# Version_2018_01.net
KiCad netlist of a schematic drawn in Altium Designer
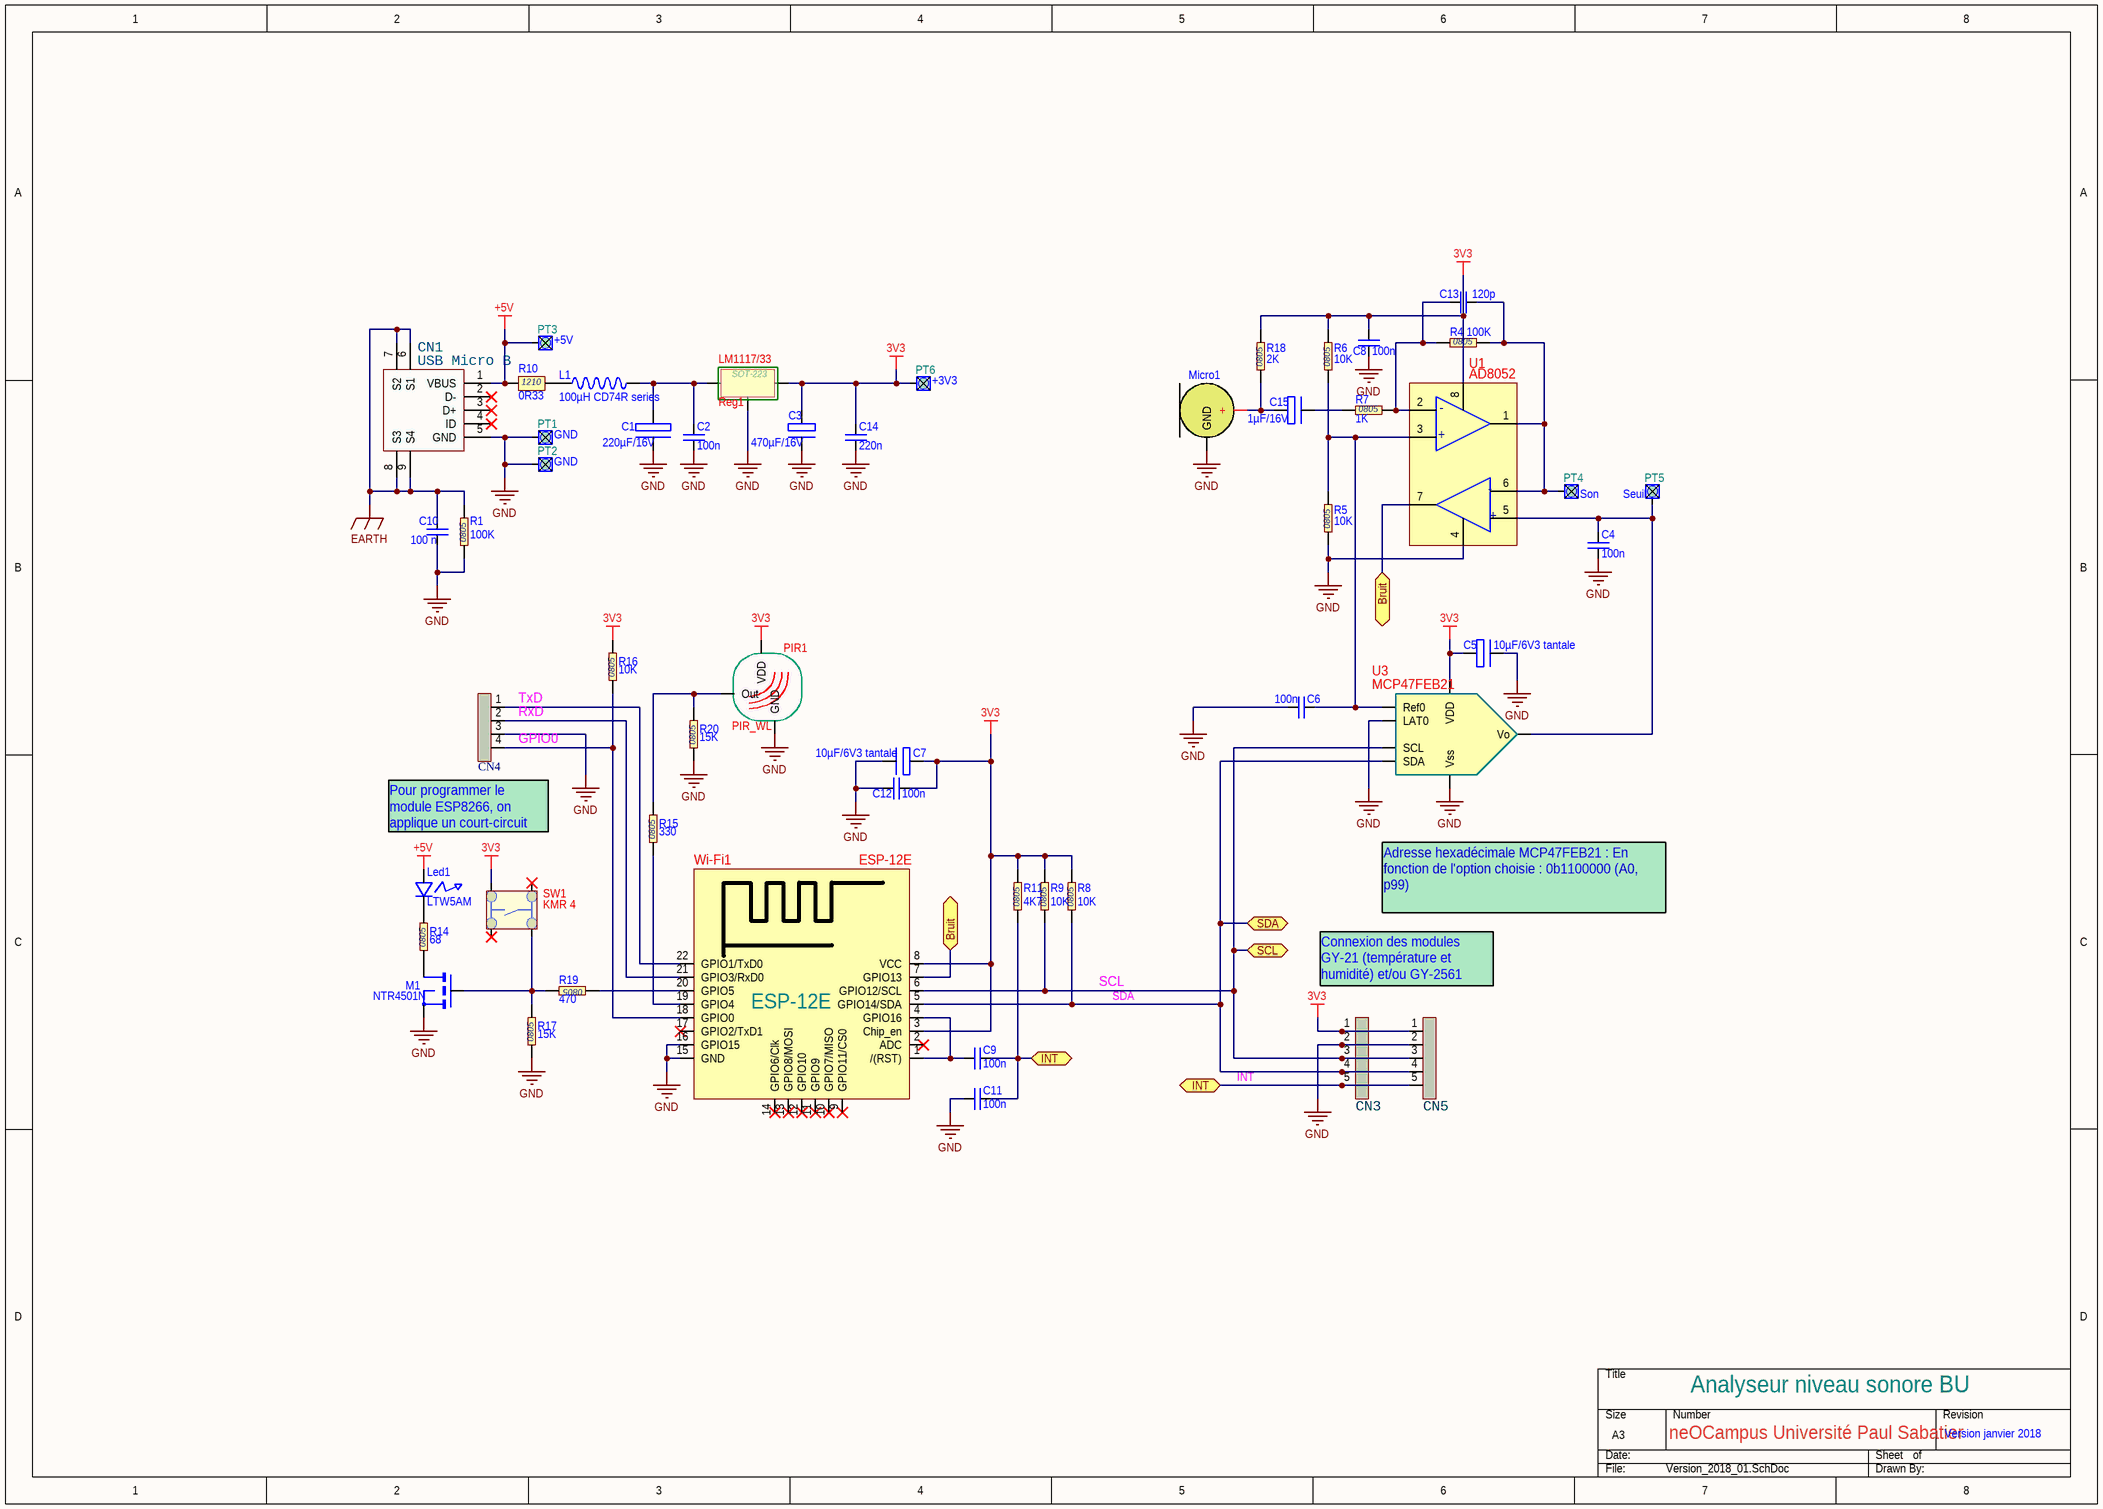
[diagram p0: Version_2018_01.SchDoc]

(export (version "E")
  (design (tool "Eeschema 10.0.6"))
  (components
    (comp (ref "C1")
      (value "220µF/16V")
      (footprint "7343-31")
      (description "253-5290 case 7343-31")
      (libsource (lib "CMS") (part "tantale 220µF/16V"))
    )
    (comp (ref "C2")
      (value "100n")
      (footprint "0805")
      (description "CMS 0805")
      (libsource (lib "CMS") (part "Cap_CMS_0805"))
    )
    (comp (ref "C3")
      (value "470µF/16V")
      (footprint "47µF/16V")
      (description "électrochimique diam. 6,3mm 128-1810")
      (libsource (lib "traversants") (part "47µF/16V"))
    )
    (comp (ref "C4")
      (value "100n")
      (footprint "0805")
      (description "CMS 0805")
      (libsource (lib "CMS") (part "Cap_CMS_0805"))
    )
    (comp (ref "C5")
      (value "10µF/6V3 tantale")
      (footprint "Tantale 10µF/6V3")
      (description "175-4041 ou 145-7412 case 3216-18")
      (libsource (lib "CMS") (part "tantale 10µF/6V3"))
    )
    (comp (ref "C6")
      (value "100n")
      (footprint "0805")
      (description "CMS 0805")
      (libsource (lib "CMS") (part "Cap_CMS_0805"))
    )
    (comp (ref "C7")
      (value "10µF/6V3 tantale")
      (footprint "Tantale 10µF/6V3")
      (description "175-4041 ou 145-7412 case 3216-18")
      (libsource (lib "CMS") (part "tantale 10µF/6V3"))
    )
    (comp (ref "C8")
      (value "100n")
      (footprint "0805")
      (description "CMS 0805")
      (libsource (lib "CMS") (part "Cap_CMS_0805"))
    )
    (comp (ref "C9")
      (value "100n")
      (footprint "0805")
      (description "CMS 0805")
      (libsource (lib "CMS") (part "Cap_CMS_0805"))
    )
    (comp (ref "C10")
      (value "100 n")
      (footprint "0805")
      (description "CMS 0805")
      (libsource (lib "CMS") (part "Cap_CMS_0805"))
    )
    (comp (ref "C11")
      (value "100n")
      (footprint "0805")
      (description "CMS 0805")
      (libsource (lib "CMS") (part "Cap_CMS_0805"))
    )
    (comp (ref "C12")
      (value "100n")
      (footprint "0805")
      (description "CMS 0805")
      (libsource (lib "CMS") (part "Cap_CMS_0805"))
    )
    (comp (ref "C13")
      (value "120p")
      (footprint "0805")
      (description "CMS 0805")
      (libsource (lib "CMS") (part "Cap_CMS_0805"))
    )
    (comp (ref "C14")
      (value "220n")
      (footprint "0805")
      (description "CMS 0805")
      (libsource (lib "CMS") (part "Cap_CMS_0805"))
    )
    (comp (ref "C15")
      (value "1µF/16V")
      (footprint "3216-18")
      (description "145-7406 case 3216-18")
      (libsource (lib "CMS") (part "tantale 1µF/16V"))
    )
    (comp (ref "CN1")
      (value "USB Micro B")
      (footprint "USB Micro 714-2347")
      (description "Amphenol 714-2347")
      (libsource (lib "Connecteurs Contacts") (part "USB Micro B"))
    )
    (comp (ref "CN3")
      (value "inch_ligne 1x5")
      (footprint "INCH_1x5_droit")
      (description "Inch_1x5_droit")
      (libsource (lib "Connecteurs Contacts") (part "Inch_1x5_droit"))
    )
    (comp (ref "CN4")
      (value "inch_ligne 1x4")
      (footprint "INCH_1x4_droit")
      (description "Inch_1x4_droit")
      (libsource (lib "Connecteurs Contacts") (part "Inch_1x4_droit"))
    )
    (comp (ref "CN5")
      (value "inch_ligne 1x5")
      (footprint "INCH_1x5_droit")
      (description "Inch_1x5_droit")
      (libsource (lib "Connecteurs Contacts") (part "Inch_1x5_droit"))
    )
    (comp (ref "L1")
      (value "100µH CD74R series")
      (footprint "SELF CD74R")
      (description "SMT CD74R Aliexpress")
      (libsource (lib "CMS") (part "Self CD74R"))
    )
    (comp (ref "Led1")
      (value "LTW5AM")
      (footprint "LTW5AM")
      (description "LED Golden Dragon Plus")
      (libsource (lib "CMS") (part "LTW5AM LED"))
    )
    (comp (ref "M1")
      (value "NTR4501N")
      (footprint "SOT23 (NTR4501)")
      (description "MOSFET canal N")
      (libsource (lib "Transistors Bip Mos IGBT") (part "NTR4501N"))
    )
    (comp (ref "Micro1")
      (value "Electret")
      (footprint "Micro_electret simple")
      (description "Microphone électret")
      (libsource (lib "traversants") (part "Microphone_03"))
    )
    (comp (ref "PIR1")
      (value "PIR_WL")
      (footprint "PIR_WL")
      (description "Détecteur infrarouge")
      (libsource (lib "traversants") (part "PIR_01"))
    )
    (comp (ref "PT1")
      (value "GND")
      (footprint "PTEST boucle")
      (description "pointe de test CI 262-2179")
      (libsource (lib "Connecteurs Contacts") (part "PTEST boucle"))
    )
    (comp (ref "PT2")
      (value "GND")
      (footprint "PTEST boucle")
      (description "pointe de test CI 262-2179")
      (libsource (lib "Connecteurs Contacts") (part "PTEST boucle"))
    )
    (comp (ref "PT3")
      (value "+5V")
      (footprint "PTEST boucle")
      (description "pointe de test CI 262-2179")
      (libsource (lib "Connecteurs Contacts") (part "PTEST boucle"))
    )
    (comp (ref "PT4")
      (value "Son")
      (footprint "PTEST boucle")
      (description "pointe de test CI 262-2179")
      (libsource (lib "Connecteurs Contacts") (part "PTEST boucle"))
    )
    (comp (ref "PT5")
      (value "Seuil")
      (footprint "PTEST boucle")
      (description "pointe de test CI 262-2179")
      (libsource (lib "Connecteurs Contacts") (part "PTEST boucle"))
    )
    (comp (ref "PT6")
      (value "+3V3")
      (footprint "PTEST boucle")
      (description "pointe de test CI 262-2179")
      (libsource (lib "Connecteurs Contacts") (part "PTEST boucle"))
    )
    (comp (ref "R1")
      (value "100K")
      (footprint "0805")
      (description "CMS 0805")
      (libsource (lib "") (part "Res CMS 0805_1"))
    )
    (comp (ref "R4")
      (value "100K")
      (footprint "0805")
      (description "CMS 0805")
      (libsource (lib "CMS") (part "Res CMS 0805"))
    )
    (comp (ref "R5")
      (value "10K")
      (footprint "0805")
      (description "CMS 0805")
      (libsource (lib "") (part "Res CMS 0805_1"))
    )
    (comp (ref "R6")
      (value "10K")
      (footprint "0805")
      (description "CMS 0805")
      (libsource (lib "") (part "Res CMS 0805_1"))
    )
    (comp (ref "R7")
      (value "1K")
      (footprint "0805")
      (description "CMS 0805")
      (libsource (lib "CMS") (part "Res CMS 0805"))
    )
    (comp (ref "R8")
      (value "10K")
      (footprint "0805")
      (description "CMS 0805")
      (libsource (lib "") (part "Res CMS 0805_1"))
    )
    (comp (ref "R9")
      (value "10K")
      (footprint "0805")
      (description "CMS 0805")
      (libsource (lib "") (part "Res CMS 0805_1"))
    )
    (comp (ref "R10")
      (value "0R33")
      (footprint "1210")
      (description "CMS 1210")
      (libsource (lib "CMS") (part "Res CMS 1210 ERJ14B"))
    )
    (comp (ref "R11")
      (value "4K7")
      (footprint "0805")
      (description "CMS 0805")
      (libsource (lib "") (part "Res CMS 0805_1"))
    )
    (comp (ref "R14")
      (value "68")
      (footprint "0805")
      (description "CMS 0805")
      (libsource (lib "") (part "Res CMS 0805_1"))
    )
    (comp (ref "R15")
      (value "330")
      (footprint "0805")
      (description "CMS 0805")
      (libsource (lib "") (part "Res CMS 0805_1"))
    )
    (comp (ref "R16")
      (value "10K")
      (footprint "0805")
      (description "CMS 0805")
      (libsource (lib "") (part "Res CMS 0805_1"))
    )
    (comp (ref "R17")
      (value "15K")
      (footprint "0805")
      (description "CMS 0805")
      (libsource (lib "") (part "Res CMS 0805_1"))
    )
    (comp (ref "R18")
      (value "2K")
      (footprint "0805")
      (description "CMS 0805")
      (libsource (lib "") (part "Res CMS 0805_1"))
    )
    (comp (ref "R19")
      (value "470")
      (footprint "0805")
      (description "CMS 0805")
      (libsource (lib "") (part "Res CMS 0805_2"))
    )
    (comp (ref "R20")
      (value "15K")
      (footprint "0805")
      (description "CMS 0805")
      (libsource (lib "") (part "Res CMS 0805_1"))
    )
    (comp (ref "Reg1")
      (value "LM1117/33")
      (footprint "SOT-223 thermo1")
      (description "Régulateur SOT-223")
      (libsource (lib "Convertisseurs_Régulateurs") (part "LM1117MPX-3.3"))
    )
    (comp (ref "SW1")
      (value "KMR 4")
      (footprint "µSwitch KMR4")
      (description "KMR 4 Series 793-1605")
      (libsource (lib "Interrupteurs Commutateurs") (part "µSwitch"))
    )
    (comp (ref "U1")
      (value "AD8052")
      (footprint "SOIC08")
      (description "AOP")
      (libsource (lib "CMS") (part "AD8052"))
    )
    (comp (ref "U3")
      (value "MCP47FEB21")
      (footprint "TSSOP_8")
      (description "DAC I2C (RS : 879-3261)")
      (libsource (lib "CMS") (part "MCP47FEB21"))
    )
    (comp (ref "Wi-Fi1")
      (value "ESP-12E")
      (footprint "ESP-12E")
      (description "ESP-12E module Wi-Fi")
      (libsource (lib "CMS") (part "ESP-12E"))
    )
  )
  (nets
    (net (code "1") (name "+5V") (class "Default")
      (node (ref "CN1") (pin "1") (pinfunction "VBUS_1") (pintype "passive"))
      (node (ref "Led1") (pin "1") (pinfunction "anode_1") (pintype "passive"))
      (node (ref "PT3") (pin "1") (pinfunction "PIN_1") (pintype "passive"))
      (node (ref "R10") (pin "1") (pinfunction "CT1_1") (pintype "passive"))
    )
    (net (code "2") (name "/Bruit") (class "Default")
      (node (ref "U1") (pin "7") (pinfunction "out_7") (pintype "passive"))
      (node (ref "Wi-Fi1") (pin "7") (pinfunction "GPIO13_7") (pintype "passive"))
    )
    (net (code "3") (name "/GPIO0") (class "Default")
      (node (ref "CN4") (pin "4") (pintype "passive"))
      (node (ref "R16") (pin "1") (pinfunction "CT1_1") (pintype "passive"))
      (node (ref "Wi-Fi1") (pin "18") (pinfunction "GPIO0_18") (pintype "passive"))
    )
    (net (code "4") (name "/INT") (class "Default")
      (node (ref "C11") (pin "2") (pinfunction "CT2_2") (pintype "passive"))
      (node (ref "C9") (pin "1") (pinfunction "CT1_1") (pintype "passive"))
      (node (ref "CN3") (pin "5") (pintype "passive"))
      (node (ref "CN5") (pin "5") (pintype "passive"))
      (node (ref "R11") (pin "1") (pinfunction "CT1_1") (pintype "passive"))
    )
    (net (code "5") (name "/RxD") (class "Default")
      (node (ref "CN4") (pin "2") (pintype "passive"))
      (node (ref "Wi-Fi1") (pin "21") (pinfunction "GPIO3/RxD0_21") (pintype "passive"))
    )
    (net (code "6") (name "/SCL") (class "Default")
      (node (ref "CN3") (pin "3") (pintype "passive"))
      (node (ref "CN5") (pin "3") (pintype "passive"))
      (node (ref "R9") (pin "1") (pinfunction "CT1_1") (pintype "passive"))
      (node (ref "U3") (pin "7") (pinfunction "SCL_7") (pintype "passive"))
      (node (ref "Wi-Fi1") (pin "6") (pinfunction "GPIO12/SCL_6") (pintype "passive"))
    )
    (net (code "7") (name "/SDA") (class "Default")
      (node (ref "CN3") (pin "4") (pintype "passive"))
      (node (ref "CN5") (pin "4") (pintype "passive"))
      (node (ref "R8") (pin "1") (pinfunction "CT1_1") (pintype "passive"))
      (node (ref "U3") (pin "8") (pinfunction "SDA_8") (pintype "passive"))
      (node (ref "Wi-Fi1") (pin "5") (pinfunction "GPIO14/SDA_5") (pintype "passive"))
    )
    (net (code "8") (name "/TxD") (class "Default")
      (node (ref "CN4") (pin "1") (pintype "passive"))
      (node (ref "Wi-Fi1") (pin "22") (pinfunction "GPIO1/TxD0_22") (pintype "passive"))
    )
    (net (code "9") (name "3V3") (class "Default")
      (node (ref "C12") (pin "2") (pinfunction "CT2_2") (pintype "passive"))
      (node (ref "C14") (pin "2") (pinfunction "CT2_2") (pintype "passive"))
      (node (ref "C3") (pin "1") (pinfunction "V+_1") (pintype "passive"))
      (node (ref "C5") (pin "1") (pinfunction "V+_1") (pintype "passive"))
      (node (ref "C7") (pin "1") (pinfunction "V+_1") (pintype "passive"))
      (node (ref "C8") (pin "2") (pinfunction "CT2_2") (pintype "passive"))
      (node (ref "CN3") (pin "1") (pintype "passive"))
      (node (ref "CN5") (pin "1") (pintype "passive"))
      (node (ref "PIR1") (pin "1") (pinfunction "VDD_1") (pintype "passive"))
      (node (ref "PT6") (pin "1") (pinfunction "PIN_1") (pintype "passive"))
      (node (ref "R11") (pin "2") (pinfunction "CT2_2") (pintype "passive"))
      (node (ref "R16") (pin "2") (pinfunction "CT2_2") (pintype "passive"))
      (node (ref "R18") (pin "2") (pinfunction "CT2_2") (pintype "passive"))
      (node (ref "R6") (pin "2") (pinfunction "CT2_2") (pintype "passive"))
      (node (ref "R8") (pin "2") (pinfunction "CT2_2") (pintype "passive"))
      (node (ref "R9") (pin "2") (pinfunction "CT2_2") (pintype "passive"))
      (node (ref "Reg1") (pin "2") (pinfunction "OUT_2") (pintype "passive"))
      (node (ref "SW1") (pin "2") (pinfunction "CT2_2") (pintype "passive"))
      (node (ref "U1") (pin "8") (pinfunction "V+_8") (pintype "passive"))
      (node (ref "U3") (pin "1") (pinfunction "VDD_1") (pintype "passive"))
      (node (ref "Wi-Fi1") (pin "3") (pinfunction "Chip_en_3") (pintype "passive"))
      (node (ref "Wi-Fi1") (pin "8") (pinfunction "VCC_8") (pintype "passive"))
    )
    (net (code "10") (name "EARTH") (class "Default")
      (node (ref "C10") (pin "2") (pinfunction "CT2_2") (pintype "passive"))
      (node (ref "CN1") (pin "6") (pinfunction "S1_6") (pintype "passive"))
      (node (ref "CN1") (pin "7") (pinfunction "S2_7") (pintype "passive"))
      (node (ref "CN1") (pin "8") (pinfunction "S3_8") (pintype "passive"))
      (node (ref "CN1") (pin "9") (pinfunction "S4_9") (pintype "passive"))
      (node (ref "R1") (pin "2") (pinfunction "CT2_2") (pintype "passive"))
    )
    (net (code "11") (name "GND") (class "Default")
      (node (ref "C1") (pin "2") (pinfunction "V-_2") (pintype "passive"))
      (node (ref "C10") (pin "1") (pinfunction "CT1_1") (pintype "passive"))
      (node (ref "C11") (pin "1") (pinfunction "CT1_1") (pintype "passive"))
      (node (ref "C12") (pin "1") (pinfunction "CT1_1") (pintype "passive"))
      (node (ref "C14") (pin "1") (pinfunction "CT1_1") (pintype "passive"))
      (node (ref "C2") (pin "1") (pinfunction "CT1_1") (pintype "passive"))
      (node (ref "C3") (pin "2") (pinfunction "V-_2") (pintype "passive"))
      (node (ref "C4") (pin "1") (pinfunction "CT1_1") (pintype "passive"))
      (node (ref "C5") (pin "2") (pinfunction "V-_2") (pintype "passive"))
      (node (ref "C6") (pin "2") (pinfunction "CT2_2") (pintype "passive"))
      (node (ref "C7") (pin "2") (pinfunction "V-_2") (pintype "passive"))
      (node (ref "C8") (pin "1") (pinfunction "CT1_1") (pintype "passive"))
      (node (ref "CN1") (pin "5") (pinfunction "GND_5") (pintype "passive"))
      (node (ref "CN3") (pin "2") (pintype "passive"))
      (node (ref "CN4") (pin "3") (pintype "passive"))
      (node (ref "CN5") (pin "2") (pintype "passive"))
      (node (ref "M1") (pin "3") (pinfunction "S_3") (pintype "passive"))
      (node (ref "Micro1") (pin "0") (pinfunction "GND_0") (pintype "passive"))
      (node (ref "PIR1") (pin "3") (pinfunction "GND_3") (pintype "passive"))
      (node (ref "PT1") (pin "1") (pinfunction "PIN_1") (pintype "passive"))
      (node (ref "PT2") (pin "1") (pinfunction "PIN_1") (pintype "passive"))
      (node (ref "R1") (pin "1") (pinfunction "CT1_1") (pintype "passive"))
      (node (ref "R17") (pin "1") (pinfunction "CT1_1") (pintype "passive"))
      (node (ref "R20") (pin "1") (pinfunction "CT1_1") (pintype "passive"))
      (node (ref "R5") (pin "1") (pinfunction "CT1_1") (pintype "passive"))
      (node (ref "Reg1") (pin "1") (pinfunction "GND_1") (pintype "passive"))
      (node (ref "U1") (pin "4") (pinfunction "V-_4") (pintype "passive"))
      (node (ref "U3") (pin "5") (pinfunction "Vss_5") (pintype "passive"))
      (node (ref "U3") (pin "6") (pinfunction "LAT0_6") (pintype "passive"))
      (node (ref "Wi-Fi1") (pin "15") (pinfunction "GND_15") (pintype "passive"))
      (node (ref "Wi-Fi1") (pin "16") (pinfunction "GPIO15_16") (pintype "passive"))
    )
    (net (code "12") (name "Net-(C1-V+)") (class "Default")
      (node (ref "C1") (pin "1") (pinfunction "V+_1") (pintype "passive"))
      (node (ref "C2") (pin "2") (pinfunction "CT2_2") (pintype "passive"))
      (node (ref "L1") (pin "1") (pinfunction "CT1_1") (pintype "passive"))
      (node (ref "Reg1") (pin "3") (pinfunction "IN_3") (pintype "passive"))
    )
    (net (code "13") (name "Net-(C4-CT2)") (class "Default")
      (node (ref "C4") (pin "2") (pinfunction "CT2_2") (pintype "passive"))
      (node (ref "PT5") (pin "1") (pinfunction "PIN_1") (pintype "passive"))
      (node (ref "U1") (pin "5") (pinfunction "in+_5") (pintype "passive"))
      (node (ref "U3") (pin "3") (pinfunction "Vo_3") (pintype "passive"))
    )
    (net (code "14") (name "Net-(C6-CT1)") (class "Default")
      (node (ref "C6") (pin "1") (pinfunction "CT1_1") (pintype "passive"))
      (node (ref "R5") (pin "2") (pinfunction "CT2_2") (pintype "passive"))
      (node (ref "R6") (pin "1") (pinfunction "CT1_1") (pintype "passive"))
      (node (ref "U1") (pin "3") (pinfunction "in+_3") (pintype "passive"))
      (node (ref "U3") (pin "2") (pinfunction "Ref0_2") (pintype "passive"))
    )
    (net (code "15") (name "Net-(C9-CT2)") (class "Default")
      (node (ref "C9") (pin "2") (pinfunction "CT2_2") (pintype "passive"))
      (node (ref "Wi-Fi1") (pin "1") (pinfunction "/(RST)_1") (pintype "passive"))
      (node (ref "Wi-Fi1") (pin "4") (pinfunction "GPIO16_4") (pintype "passive"))
    )
    (net (code "16") (name "Net-(C13-CT1)") (class "Default")
      (node (ref "C13") (pin "1") (pinfunction "CT1_1") (pintype "passive"))
      (node (ref "R4") (pin "1") (pinfunction "CT1_1") (pintype "passive"))
      (node (ref "R7") (pin "2") (pinfunction "CT2_2") (pintype "passive"))
      (node (ref "U1") (pin "2") (pinfunction "in-_2") (pintype "passive"))
    )
    (net (code "17") (name "Net-(C13-CT2)") (class "Default")
      (node (ref "C13") (pin "2") (pinfunction "CT2_2") (pintype "passive"))
      (node (ref "PT4") (pin "1") (pinfunction "PIN_1") (pintype "passive"))
      (node (ref "R4") (pin "2") (pinfunction "CT2_2") (pintype "passive"))
      (node (ref "U1") (pin "1") (pinfunction "out_1") (pintype "passive"))
      (node (ref "U1") (pin "6") (pinfunction "in-_6") (pintype "passive"))
    )
    (net (code "18") (name "Net-(C15-V+)") (class "Default")
      (node (ref "C15") (pin "1") (pinfunction "V+_1") (pintype "passive"))
      (node (ref "Micro1") (pin "1") (pinfunction "+_1") (pintype "passive"))
      (node (ref "R18") (pin "1") (pinfunction "CT1_1") (pintype "passive"))
    )
    (net (code "19") (name "Net-(C15-V-)") (class "Default")
      (node (ref "C15") (pin "2") (pinfunction "V-_2") (pintype "passive"))
      (node (ref "R7") (pin "1") (pinfunction "CT1_1") (pintype "passive"))
    )
    (net (code "20") (name "Net-(L1-CT2)") (class "Default")
      (node (ref "L1") (pin "2") (pinfunction "CT2_2") (pintype "passive"))
      (node (ref "R10") (pin "2") (pinfunction "CT2_2") (pintype "passive"))
    )
    (net (code "21") (name "Net-(Led1-cathode)") (class "Default")
      (node (ref "Led1") (pin "2") (pinfunction "cathode_2") (pintype "passive"))
      (node (ref "R14") (pin "2") (pinfunction "CT2_2") (pintype "passive"))
    )
    (net (code "22") (name "Net-(M1-D)") (class "Default")
      (node (ref "M1") (pin "1") (pinfunction "D_1") (pintype "passive"))
      (node (ref "R14") (pin "1") (pinfunction "CT1_1") (pintype "passive"))
    )
    (net (code "23") (name "Net-(M1-G)") (class "Default")
      (node (ref "M1") (pin "2") (pinfunction "G_2") (pintype "passive"))
      (node (ref "R17") (pin "2") (pinfunction "CT2_2") (pintype "passive"))
      (node (ref "R19") (pin "2") (pinfunction "CT2_2") (pintype "passive"))
      (node (ref "SW1") (pin "3") (pinfunction "CT3_3") (pintype "passive"))
    )
    (net (code "24") (name "Net-(PIR1-Out)") (class "Default")
      (node (ref "PIR1") (pin "2") (pinfunction "Out_2") (pintype "passive"))
      (node (ref "R15") (pin "2") (pinfunction "CT2_2") (pintype "passive"))
      (node (ref "R20") (pin "2") (pinfunction "CT2_2") (pintype "passive"))
    )
    (net (code "25") (name "Net-(R15-CT1)") (class "Default")
      (node (ref "R15") (pin "1") (pinfunction "CT1_1") (pintype "passive"))
      (node (ref "Wi-Fi1") (pin "19") (pinfunction "GPIO4_19") (pintype "passive"))
    )
    (net (code "26") (name "Net-(R19-CT1)") (class "Default")
      (node (ref "R19") (pin "1") (pinfunction "CT1_1") (pintype "passive"))
      (node (ref "Wi-Fi1") (pin "20") (pinfunction "GPIO5_20") (pintype "passive"))
    )
    (net (code "27") (name "unconnected-(CN1-D+-Pad3)") (class "Default")
      (node (ref "CN1") (pin "3") (pinfunction "D+_3") (pintype "passive+no_connect"))
    )
    (net (code "28") (name "unconnected-(CN1-D--Pad2)") (class "Default")
      (node (ref "CN1") (pin "2") (pinfunction "D-_2") (pintype "passive+no_connect"))
    )
    (net (code "29") (name "unconnected-(CN1-ID-Pad4)") (class "Default")
      (node (ref "CN1") (pin "4") (pinfunction "ID_4") (pintype "passive+no_connect"))
    )
    (net (code "30") (name "unconnected-(SW1-CT1-Pad1)") (class "Default")
      (node (ref "SW1") (pin "1") (pinfunction "CT1_1") (pintype "passive+no_connect"))
    )
    (net (code "31") (name "unconnected-(SW1-CT4-Pad4)") (class "Default")
      (node (ref "SW1") (pin "4") (pinfunction "CT4_4") (pintype "passive+no_connect"))
    )
    (net (code "32") (name "unconnected-(Wi-Fi1-ADC-Pad2)") (class "Default")
      (node (ref "Wi-Fi1") (pin "2") (pinfunction "ADC_2") (pintype "passive+no_connect"))
    )
    (net (code "33") (name "unconnected-(Wi-Fi1-GPIO2{slash}TxD1-Pad17)") (class "Default")
      (node (ref "Wi-Fi1") (pin "17") (pinfunction "GPIO2/TxD1_17") (pintype "passive+no_connect"))
    )
    (net (code "34") (name "unconnected-(Wi-Fi1-GPIO6{slash}Clk-Pad14)") (class "Default")
      (node (ref "Wi-Fi1") (pin "14") (pinfunction "GPIO6/Clk_14") (pintype "passive+no_connect"))
    )
    (net (code "35") (name "unconnected-(Wi-Fi1-GPIO7{slash}MISO-Pad10)") (class "Default")
      (node (ref "Wi-Fi1") (pin "10") (pinfunction "GPIO7/MISO_10") (pintype "passive+no_connect"))
    )
    (net (code "36") (name "unconnected-(Wi-Fi1-GPIO8{slash}MOSI-Pad13)") (class "Default")
      (node (ref "Wi-Fi1") (pin "13") (pinfunction "GPIO8/MOSI_13") (pintype "passive+no_connect"))
    )
    (net (code "37") (name "unconnected-(Wi-Fi1-GPIO9-Pad11)") (class "Default")
      (node (ref "Wi-Fi1") (pin "11") (pinfunction "GPIO9_11") (pintype "passive+no_connect"))
    )
    (net (code "38") (name "unconnected-(Wi-Fi1-GPIO10-Pad12)") (class "Default")
      (node (ref "Wi-Fi1") (pin "12") (pinfunction "GPIO10_12") (pintype "passive+no_connect"))
    )
    (net (code "39") (name "unconnected-(Wi-Fi1-GPIO11{slash}CS0-Pad9)") (class "Default")
      (node (ref "Wi-Fi1") (pin "9") (pinfunction "GPIO11/CS0_9") (pintype "passive+no_connect"))
    )
  )
)
